# WIZARD_Control.net
KiCad netlist of a schematic drawn in Altium Designer
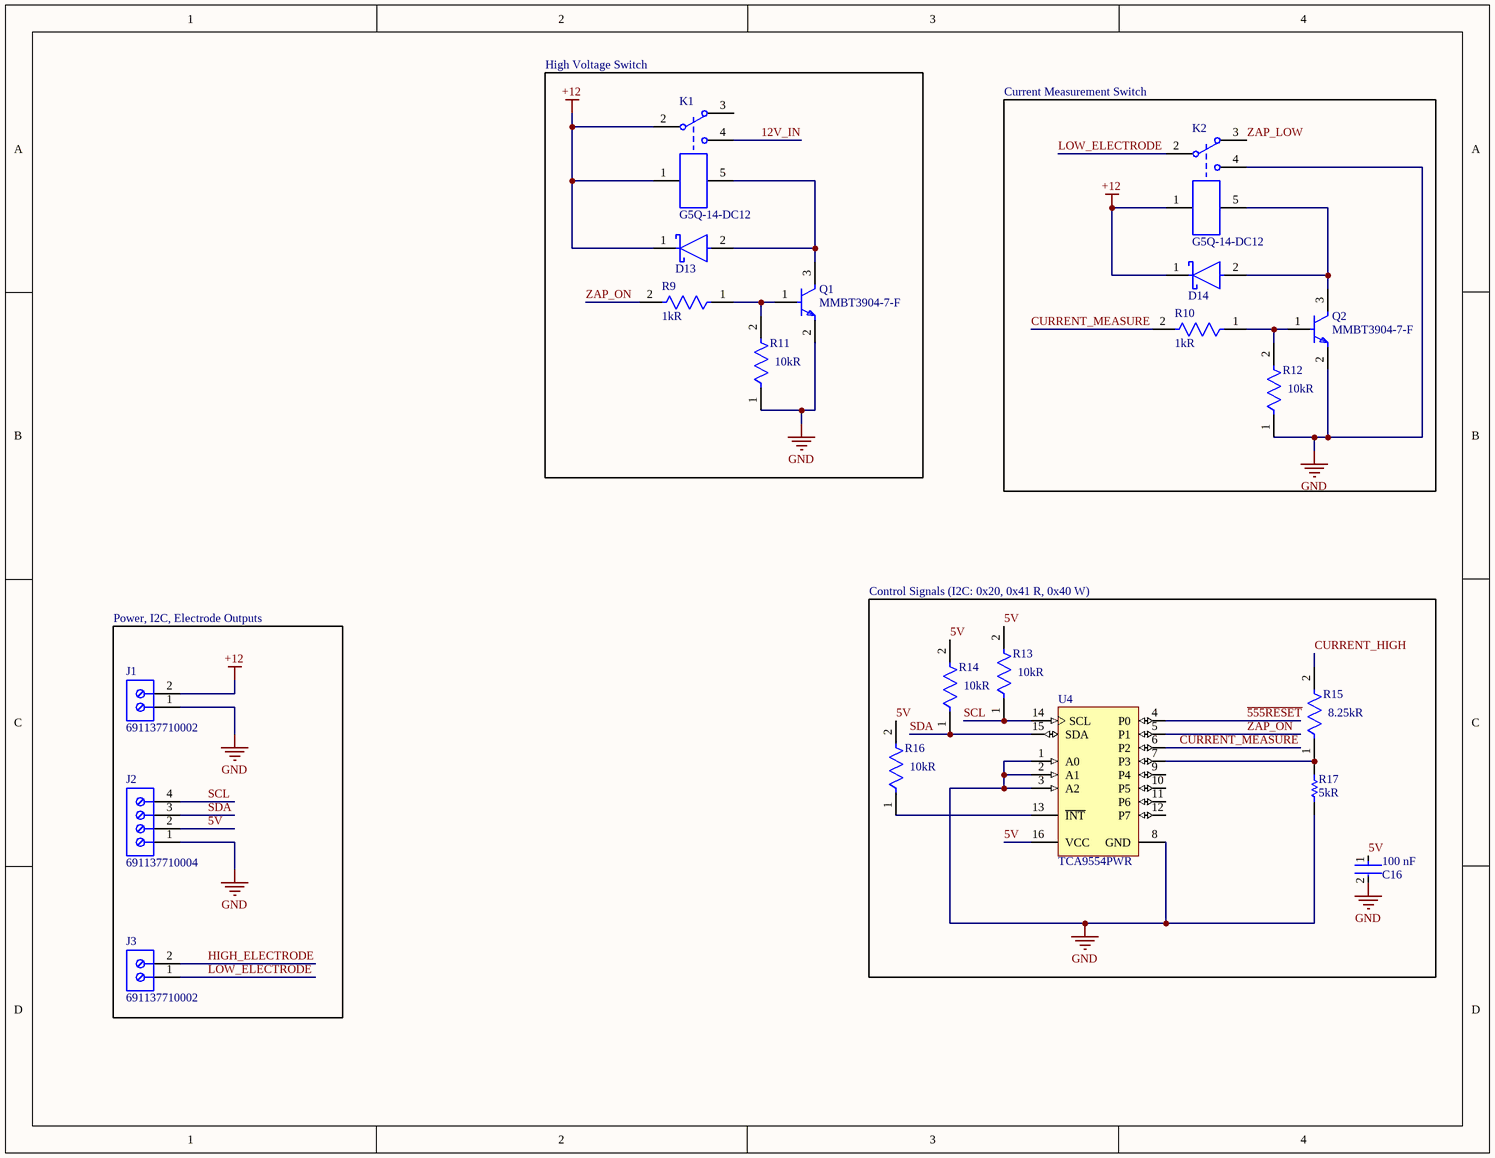
[diagram p0: WIZARD_Control.SchDoc]

(export (version "E")
  (design (tool "Eeschema 10.0.6"))
  (components
    (comp (ref "C16")
      (value "CC0805KRX7R9BB104")
      (footprint "FP-CC0805-0_85-MFG")
      (description "CAP CER 0.1UF 50V X7R 0805")
      (fields
        (field (name "TOLERANCE") "0.1")
        (field (name "CAPACITANCE") "100 nF")
        (field (name "MANUFACTURER") "Yageo")
      )
      (libsource (lib "Altium Content Vault") (part "11868f565c42a9108669ba33697ecf6"))
    )
    (comp (ref "D13")
      (value "SK520B")
      (footprint "FP-SMB-MFG")
      (description "SK520B Diode Schottky 200V 5A Smb")
      (libsource (lib "Altium Content Vault") (part "c1678fac7984e62e0809fbf79c06691"))
    )
    (comp (ref "D14")
      (value "SK520B")
      (footprint "FP-SMB-MFG")
      (description "SK520B Diode Schottky 200V 5A Smb")
      (libsource (lib "Altium Content Vault") (part "c1678fac7984e62e0809fbf79c06691"))
    )
    (comp (ref "J1")
      (value "691137710002")
      (footprint "691137710002")
      (libsource (lib "Altium Content Vault") (part "TBL - 1R - 02P - Screw"))
    )
    (comp (ref "J2")
      (value "691137710004")
      (footprint "691137710004")
      (libsource (lib "Altium Content Vault") (part "TBL - 1R - 04P - Screw"))
    )
    (comp (ref "J3")
      (value "691137710002")
      (footprint "691137710002")
      (libsource (lib "Altium Content Vault") (part "TBL - 1R - 02P - Screw"))
    )
    (comp (ref "K1")
      (value "G5Q-14-DC12")
      (footprint "OMRON-G5Q-14-5_V")
      (fields (field (name "MANUFACTURER") "Omron Electronic Components") (field (name "PARTNUMBER") "G5Q"))
      (libsource (lib "Altium Content Vault") (part "RELAY-SPDT-5_N"))
    )
    (comp (ref "K2")
      (value "G5Q-14-DC12")
      (footprint "OMRON-G5Q-14-5_V")
      (fields (field (name "MANUFACTURER") "Omron Electronic Components") (field (name "PARTNUMBER") "G5Q"))
      (libsource (lib "Altium Content Vault") (part "RELAY-SPDT-5_N"))
    )
    (comp (ref "Q1")
      (value "MMBT3904-7-F")
      (footprint "FP-SOT23-IPC_A")
      (description "TRANS NPN 40V 0.2A SMD SOT23-3")
      (libsource (lib "Altium Content Vault") (part "b44e953556f554d0102664c7d152cb4"))
    )
    (comp (ref "Q2")
      (value "MMBT3904-7-F")
      (footprint "FP-SOT23-IPC_A")
      (description "TRANS NPN 40V 0.2A SMD SOT23-3")
      (libsource (lib "Altium Content Vault") (part "b44e953556f554d0102664c7d152cb4"))
    )
    (comp (ref "R9")
      (value "RR1220P-102-D")
      (footprint "FP-RR1220-IPC_A")
      (description "1kΩ ±0.5% 0.1W 1/10W Chip Resistor 0805 (2012 Metric) Thin Film")
      (fields (field (name "TOLERANCE") "0.5%") (field (name "RESISTANCE") "1kR"))
      (libsource (lib "Altium Content Vault") (part "1029c3af85768c4190bb7ad29bc67b5"))
    )
    (comp (ref "R10")
      (value "RR1220P-102-D")
      (footprint "FP-RR1220-IPC_A")
      (description "1kΩ ±0.5% 0.1W 1/10W Chip Resistor 0805 (2012 Metric) Thin Film")
      (fields (field (name "TOLERANCE") "0.5%") (field (name "RESISTANCE") "1kR"))
      (libsource (lib "Altium Content Vault") (part "1029c3af85768c4190bb7ad29bc67b5"))
    )
    (comp (ref "R11")
      (value "RR1220P-103-D")
      (footprint "FP-RR1220-IPC_A")
      (description "10kΩ ±0.5% 0.1W 1/10W Chip Resistor 0805 (2012 Metric) Thin Film")
      (fields (field (name "RESISTANCE") "10kR") (field (name "TOLERANCE") "0.5%"))
      (libsource (lib "Altium Content Vault") (part "1029c3af85768c4190bb7ad29bc67b5"))
    )
    (comp (ref "R12")
      (value "RR1220P-103-D")
      (footprint "FP-RR1220-IPC_A")
      (description "10kΩ ±0.5% 0.1W 1/10W Chip Resistor 0805 (2012 Metric) Thin Film")
      (fields (field (name "RESISTANCE") "10kR") (field (name "TOLERANCE") "0.5%"))
      (libsource (lib "Altium Content Vault") (part "1029c3af85768c4190bb7ad29bc67b5"))
    )
    (comp (ref "R13")
      (value "RR1220P-103-D")
      (footprint "FP-RR1220-IPC_A")
      (description "10kΩ ±0.5% 0.1W 1/10W Chip Resistor 0805 (2012 Metric) Thin Film")
      (fields (field (name "RESISTANCE") "10kR") (field (name "TOLERANCE") "0.5%"))
      (libsource (lib "Altium Content Vault") (part "1029c3af85768c4190bb7ad29bc67b5"))
    )
    (comp (ref "R14")
      (value "RR1220P-103-D")
      (footprint "FP-RR1220-IPC_A")
      (description "10kΩ ±0.5% 0.1W 1/10W Chip Resistor 0805 (2012 Metric) Thin Film")
      (fields (field (name "RESISTANCE") "10kR") (field (name "TOLERANCE") "0.5%"))
      (libsource (lib "Altium Content Vault") (part "1029c3af85768c4190bb7ad29bc67b5"))
    )
    (comp (ref "R15")
      (value "CRCW08058K25FKEA")
      (footprint "FP-CRCW0805-e3-IPC_B")
      (description "RES Thick Film, 8.25kΩ, 1%, 0.125W, 100ppm/°C, 0805")
      (fields (field (name "TOLERANCE") "1%") (field (name "RESISTANCE") "8.25kR"))
      (libsource (lib "Altium Content Vault") (part "1029c3af85768c4190bb7ad29bc67b5"))
    )
    (comp (ref "R16")
      (value "RR1220P-103-D")
      (footprint "FP-RR1220-IPC_A")
      (description "10kΩ ±0.5% 0.1W 1/10W Chip Resistor 0805 (2012 Metric) Thin Film")
      (fields (field (name "RESISTANCE") "10kR") (field (name "TOLERANCE") "0.5%"))
      (libsource (lib "Altium Content Vault") (part "1029c3af85768c4190bb7ad29bc67b5"))
    )
    (comp (ref "R17")
      (value "5kR")
      (footprint "RESC2013X50X30ML20T20")
      (fields (field (name "PART NUMBER") "CRCW08055K00FKTA") (field (name "MANUFACTURER") "Vishay Dale"))
      (libsource (lib "Altium Content Vault") (part "RES"))
    )
    (comp (ref "U4")
      (value "TCA9554PWR")
      (footprint "PW0016A_M")
      (fields (field (name "MANUFACTURER") "Texas Instruments"))
      (libsource (lib "Altium Content Vault") (part "TI-TCA9554-TSSOP_PW-16"))
    )
  )
  (nets
    (net (code "1") (name "+12") (class "Default")
      (node (ref "D13") (pin "1") (pinfunction "C_1") (pintype "passive"))
      (node (ref "D14") (pin "1") (pinfunction "C_1") (pintype "passive"))
      (node (ref "J1") (pin "2") (pinfunction "2_2") (pintype "passive"))
      (node (ref "K1") (pin "1") (pinfunction "1_1") (pintype "passive"))
      (node (ref "K1") (pin "2") (pinfunction "2_2") (pintype "passive"))
      (node (ref "K2") (pin "1") (pinfunction "1_1") (pintype "passive"))
    )
    (net (code "2") (name "/5V") (class "Default")
      (node (ref "C16") (pin "1") (pinfunction "1_1") (pintype "passive"))
      (node (ref "J2") (pin "2") (pinfunction "2_2") (pintype "passive"))
      (node (ref "R13") (pin "2") (pinfunction "2_2") (pintype "passive"))
      (node (ref "R14") (pin "2") (pinfunction "2_2") (pintype "passive"))
      (node (ref "R16") (pin "2") (pinfunction "2_2") (pintype "passive"))
      (node (ref "U4") (pin "16") (pinfunction "VCC_16") (pintype "power_in"))
    )
    (net (code "3") (name "/12V_IN") (class "Default")
      (node (ref "K1") (pin "4") (pinfunction "4_4") (pintype "passive"))
    )
    (net (code "4") (name "/CURRENT_HIGH") (class "Default")
      (node (ref "R15") (pin "2") (pinfunction "2_2") (pintype "passive"))
    )
    (net (code "5") (name "/CURRENT_MEASURE") (class "Default")
      (node (ref "R10") (pin "2") (pinfunction "2_2") (pintype "passive"))
      (node (ref "U4") (pin "6") (pinfunction "P2_6") (pintype "bidirectional"))
    )
    (net (code "6") (name "/HIGH_ELECTRODE") (class "Default")
      (node (ref "J3") (pin "2") (pinfunction "2_2") (pintype "passive"))
    )
    (net (code "7") (name "/LOW_ELECTRODE") (class "Default")
      (node (ref "J3") (pin "1") (pinfunction "1_1") (pintype "passive"))
      (node (ref "K2") (pin "2") (pinfunction "2_2") (pintype "passive"))
    )
    (net (code "8") (name "/SCL") (class "Default")
      (node (ref "J2") (pin "4") (pinfunction "4_4") (pintype "passive"))
      (node (ref "R13") (pin "1") (pinfunction "1_1") (pintype "passive"))
      (node (ref "U4") (pin "14") (pinfunction "SCL_14") (pintype "input"))
    )
    (net (code "9") (name "/SDA") (class "Default")
      (node (ref "J2") (pin "3") (pinfunction "3_3") (pintype "passive"))
      (node (ref "R14") (pin "1") (pinfunction "1_1") (pintype "passive"))
      (node (ref "U4") (pin "15") (pinfunction "SDA_15") (pintype "bidirectional"))
    )
    (net (code "10") (name "/ZAP_LOW") (class "Default")
      (node (ref "K2") (pin "3") (pinfunction "3_3") (pintype "passive"))
    )
    (net (code "11") (name "/ZAP_ON") (class "Default")
      (node (ref "R9") (pin "2") (pinfunction "2_2") (pintype "passive"))
      (node (ref "U4") (pin "5") (pinfunction "P1_5") (pintype "bidirectional"))
    )
    (net (code "12") (name "/~{555RESET}") (class "Default")
      (node (ref "U4") (pin "4") (pinfunction "P0_4") (pintype "bidirectional"))
    )
    (net (code "13") (name "GND") (class "Default")
      (node (ref "C16") (pin "2") (pinfunction "2_2") (pintype "passive"))
      (node (ref "J1") (pin "1") (pinfunction "1_1") (pintype "passive"))
      (node (ref "J2") (pin "1") (pinfunction "1_1") (pintype "passive"))
      (node (ref "K2") (pin "4") (pinfunction "4_4") (pintype "passive"))
      (node (ref "Q1") (pin "2") (pinfunction "E_2") (pintype "passive"))
      (node (ref "Q2") (pin "2") (pinfunction "E_2") (pintype "passive"))
      (node (ref "R11") (pin "1") (pinfunction "1_1") (pintype "passive"))
      (node (ref "R12") (pin "1") (pinfunction "1_1") (pintype "passive"))
      (node (ref "R17") (pin "1") (pinfunction "1_1") (pintype "passive"))
      (node (ref "U4") (pin "1") (pinfunction "A0_1") (pintype "input"))
      (node (ref "U4") (pin "2") (pinfunction "A1_2") (pintype "input"))
      (node (ref "U4") (pin "3") (pinfunction "A2_3") (pintype "input"))
      (node (ref "U4") (pin "8") (pinfunction "GND_8") (pintype "power_in"))
    )
    (net (code "14") (name "Net-(D13-A)") (class "Default")
      (node (ref "D13") (pin "2") (pinfunction "A_2") (pintype "passive"))
      (node (ref "K1") (pin "5") (pinfunction "5_5") (pintype "passive"))
      (node (ref "Q1") (pin "3") (pinfunction "C_3") (pintype "passive"))
    )
    (net (code "15") (name "Net-(D14-A)") (class "Default")
      (node (ref "D14") (pin "2") (pinfunction "A_2") (pintype "passive"))
      (node (ref "K2") (pin "5") (pinfunction "5_5") (pintype "passive"))
      (node (ref "Q2") (pin "3") (pinfunction "C_3") (pintype "passive"))
    )
    (net (code "16") (name "Net-(Q1-B)") (class "Default")
      (node (ref "Q1") (pin "1") (pinfunction "B_1") (pintype "passive"))
      (node (ref "R11") (pin "2") (pinfunction "2_2") (pintype "passive"))
      (node (ref "R9") (pin "1") (pinfunction "1_1") (pintype "passive"))
    )
    (net (code "17") (name "Net-(Q2-B)") (class "Default")
      (node (ref "Q2") (pin "1") (pinfunction "B_1") (pintype "passive"))
      (node (ref "R10") (pin "1") (pinfunction "1_1") (pintype "passive"))
      (node (ref "R12") (pin "2") (pinfunction "2_2") (pintype "passive"))
    )
    (net (code "18") (name "Net-(U4-P3)") (class "Default")
      (node (ref "R15") (pin "1") (pinfunction "1_1") (pintype "passive"))
      (node (ref "R17") (pin "2") (pinfunction "2_2") (pintype "passive"))
      (node (ref "U4") (pin "7") (pinfunction "P3_7") (pintype "bidirectional"))
    )
    (net (code "19") (name "Net-(U4-~{INT})") (class "Default")
      (node (ref "R16") (pin "1") (pinfunction "1_1") (pintype "passive"))
      (node (ref "U4") (pin "13") (pinfunction "~{INT}_13") (pintype "open_collector"))
    )
    (net (code "20") (name "unconnected-(K1-Pad3)") (class "Default")
      (node (ref "K1") (pin "3") (pinfunction "3_3") (pintype "passive"))
    )
    (net (code "21") (name "unconnected-(U4-P4-Pad9)") (class "Default")
      (node (ref "U4") (pin "9") (pinfunction "P4_9") (pintype "bidirectional"))
    )
    (net (code "22") (name "unconnected-(U4-P5-Pad10)") (class "Default")
      (node (ref "U4") (pin "10") (pinfunction "P5_10") (pintype "bidirectional"))
    )
    (net (code "23") (name "unconnected-(U4-P6-Pad11)") (class "Default")
      (node (ref "U4") (pin "11") (pinfunction "P6_11") (pintype "bidirectional"))
    )
    (net (code "24") (name "unconnected-(U4-P7-Pad12)") (class "Default")
      (node (ref "U4") (pin "12") (pinfunction "P7_12") (pintype "bidirectional"))
    )
  )
)
